# 02_-_Buttons.net
KiCad netlist of a schematic drawn in Altium Designer
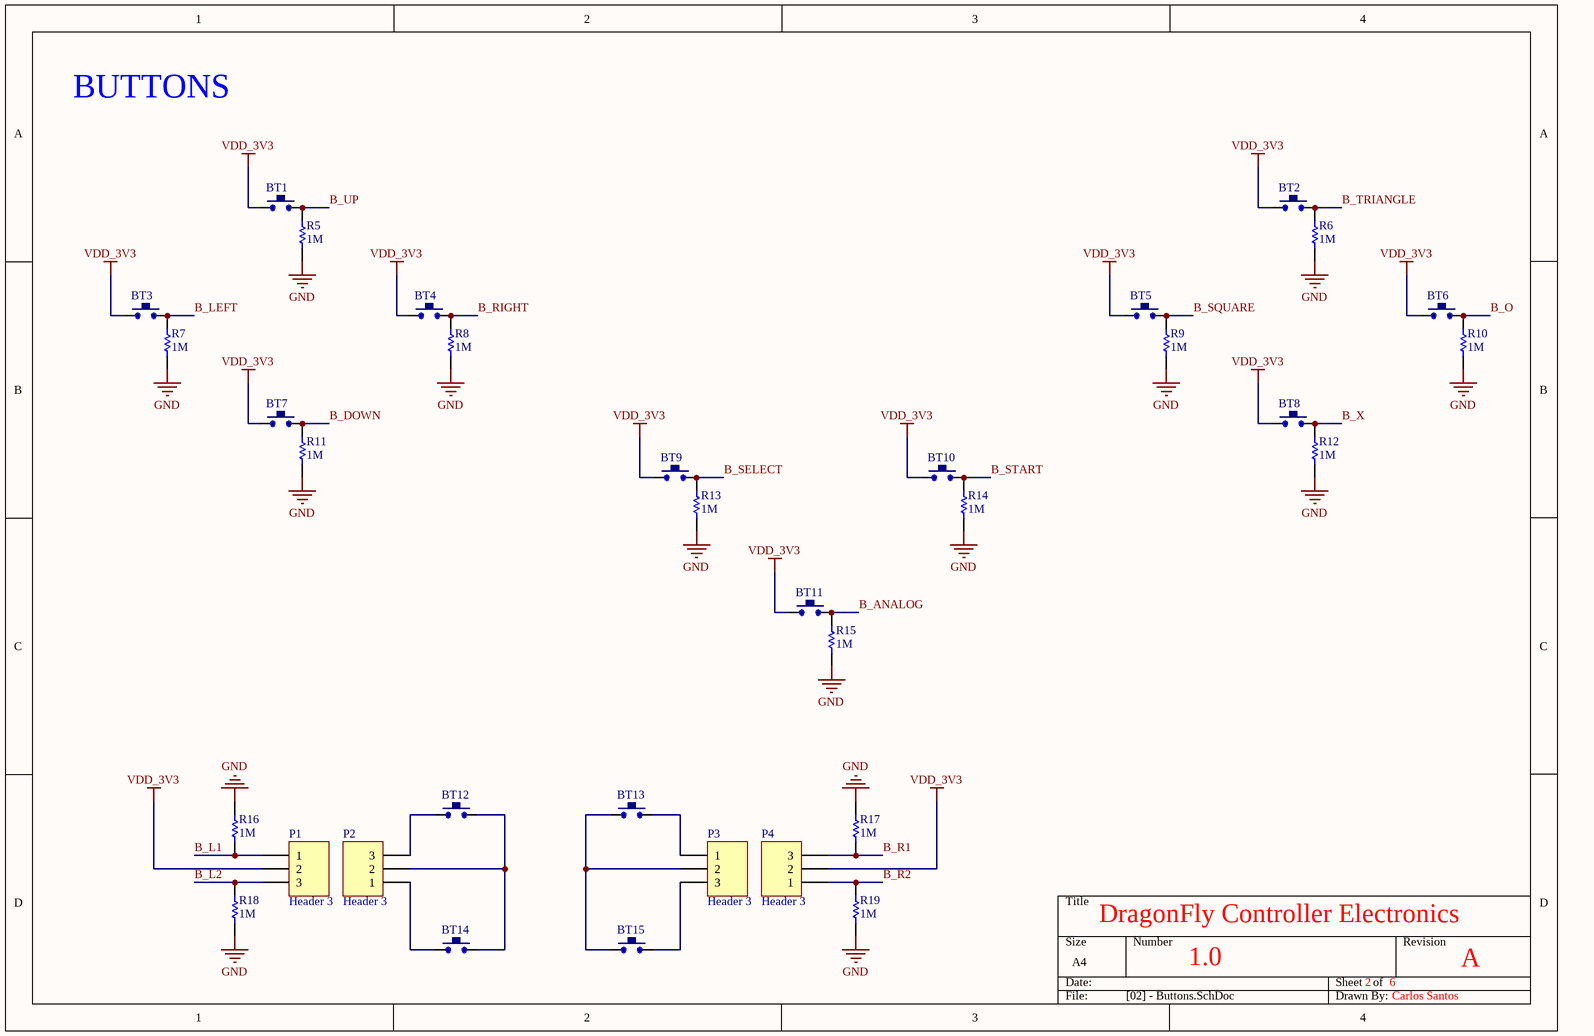
[diagram p0: [02] - Buttons.SchDoc]

(export (version "E")
  (design (tool "Eeschema 10.0.6"))
  (components
    (comp (ref "BT1")
      (value "~")
      (footprint "PCB_button_6mm_round")
      (libsource (lib "Mine") (part "PCB button"))
    )
    (comp (ref "BT2")
      (value "~")
      (footprint "PCB_button_6mm_round")
      (libsource (lib "Mine") (part "PCB button"))
    )
    (comp (ref "BT3")
      (value "~")
      (footprint "PCB_button_6mm_round")
      (libsource (lib "Mine") (part "PCB button"))
    )
    (comp (ref "BT4")
      (value "~")
      (footprint "PCB_button_6mm_round")
      (libsource (lib "Mine") (part "PCB button"))
    )
    (comp (ref "BT5")
      (value "~")
      (footprint "PCB_button_6mm_round")
      (libsource (lib "Mine") (part "PCB button"))
    )
    (comp (ref "BT6")
      (value "~")
      (footprint "PCB_button_6mm_round")
      (libsource (lib "Mine") (part "PCB button"))
    )
    (comp (ref "BT7")
      (value "~")
      (footprint "PCB_button_6mm_round")
      (libsource (lib "Mine") (part "PCB button"))
    )
    (comp (ref "BT8")
      (value "~")
      (footprint "PCB_button_6mm_round")
      (libsource (lib "Mine") (part "PCB button"))
    )
    (comp (ref "BT9")
      (value "~")
      (footprint "PCB_button_10x6mm_rect")
      (libsource (lib "Mine") (part "PCB button"))
    )
    (comp (ref "BT10")
      (value "~")
      (footprint "PCB_button_10x6mm_rect")
      (libsource (lib "Mine") (part "PCB button"))
    )
    (comp (ref "BT11")
      (value "~")
      (footprint "PCB_button_10x6mm_rect")
      (libsource (lib "Mine") (part "PCB button"))
    )
    (comp (ref "BT12")
      (value "~")
      (footprint "PCB_button_10x10mm_rect")
      (libsource (lib "Mine") (part "PCB button"))
    )
    (comp (ref "BT13")
      (value "~")
      (footprint "PCB_button_10x10mm_rect")
      (libsource (lib "Mine") (part "PCB button"))
    )
    (comp (ref "BT14")
      (value "~")
      (footprint "PCB_button_12x10mm_rect")
      (libsource (lib "Mine") (part "PCB button"))
    )
    (comp (ref "BT15")
      (value "~")
      (footprint "PCB_button_12x10mm_rect")
      (libsource (lib "Mine") (part "PCB button"))
    )
    (comp (ref "P1")
      (value "Header 3")
      (footprint "HDR1X3")
      (description "Header, 3-Pin")
      (fields (field (name "PUBLISHER") "Altium Limited"))
      (libsource (lib "") (part "Header 3_1"))
    )
    (comp (ref "P2")
      (value "Header 3")
      (footprint "HDR1X3")
      (description "Header, 3-Pin")
      (fields (field (name "PUBLISHER") "Altium Limited"))
      (libsource (lib "Miscellaneous Connectors") (part "Header 3"))
    )
    (comp (ref "P3")
      (value "Header 3")
      (footprint "HDR1X3")
      (description "Header, 3-Pin")
      (fields (field (name "PUBLISHER") "Altium Limited"))
      (libsource (lib "") (part "Header 3_1"))
    )
    (comp (ref "P4")
      (value "Header 3")
      (footprint "HDR1X3")
      (description "Header, 3-Pin")
      (fields (field (name "PUBLISHER") "Altium Limited"))
      (libsource (lib "Miscellaneous Connectors") (part "Header 3"))
    )
    (comp (ref "R5")
      (value "1M")
      (footprint "0402 - Resistor")
      (fields (field (name "Comment") "Resistor"))
      (libsource (lib "Mine") (part "Resistor"))
    )
    (comp (ref "R6")
      (value "1M")
      (footprint "0402 - Resistor")
      (fields (field (name "Comment") "Resistor"))
      (libsource (lib "Mine") (part "Resistor"))
    )
    (comp (ref "R7")
      (value "1M")
      (footprint "0402 - Resistor")
      (fields (field (name "Comment") "Resistor"))
      (libsource (lib "Mine") (part "Resistor"))
    )
    (comp (ref "R8")
      (value "1M")
      (footprint "0402 - Resistor")
      (fields (field (name "Comment") "Resistor"))
      (libsource (lib "Mine") (part "Resistor"))
    )
    (comp (ref "R9")
      (value "1M")
      (footprint "0402 - Resistor")
      (fields (field (name "Comment") "Resistor"))
      (libsource (lib "Mine") (part "Resistor"))
    )
    (comp (ref "R10")
      (value "1M")
      (footprint "0402 - Resistor")
      (fields (field (name "Comment") "Resistor"))
      (libsource (lib "Mine") (part "Resistor"))
    )
    (comp (ref "R11")
      (value "1M")
      (footprint "0402 - Resistor")
      (fields (field (name "Comment") "Resistor"))
      (libsource (lib "Mine") (part "Resistor"))
    )
    (comp (ref "R12")
      (value "1M")
      (footprint "0402 - Resistor")
      (fields (field (name "Comment") "Resistor"))
      (libsource (lib "Mine") (part "Resistor"))
    )
    (comp (ref "R13")
      (value "1M")
      (footprint "0402 - Resistor")
      (fields (field (name "Comment") "Resistor"))
      (libsource (lib "Mine") (part "Resistor"))
    )
    (comp (ref "R14")
      (value "1M")
      (footprint "0402 - Resistor")
      (fields (field (name "Comment") "Resistor"))
      (libsource (lib "Mine") (part "Resistor"))
    )
    (comp (ref "R15")
      (value "1M")
      (footprint "0402 - Resistor")
      (fields (field (name "Comment") "Resistor"))
      (libsource (lib "Mine") (part "Resistor"))
    )
    (comp (ref "R16")
      (value "1M")
      (footprint "0402 - Resistor")
      (fields (field (name "Comment") "Resistor"))
      (libsource (lib "Mine") (part "Resistor"))
    )
    (comp (ref "R17")
      (value "1M")
      (footprint "0402 - Resistor")
      (fields (field (name "Comment") "Resistor"))
      (libsource (lib "Mine") (part "Resistor"))
    )
    (comp (ref "R18")
      (value "1M")
      (footprint "0402 - Resistor")
      (fields (field (name "Comment") "Resistor"))
      (libsource (lib "Mine") (part "Resistor"))
    )
    (comp (ref "R19")
      (value "1M")
      (footprint "0402 - Resistor")
      (fields (field (name "Comment") "Resistor"))
      (libsource (lib "Mine") (part "Resistor"))
    )
  )
  (nets
    (net (code "1") (name "/B_ANALOG") (class "Default")
      (node (ref "BT11") (pin "2") (pinfunction "2_2") (pintype "passive"))
      (node (ref "R15") (pin "2") (pinfunction "2_2") (pintype "passive"))
    )
    (net (code "2") (name "/B_DOWN") (class "Default")
      (node (ref "BT7") (pin "2") (pinfunction "2_2") (pintype "passive"))
      (node (ref "R11") (pin "2") (pinfunction "2_2") (pintype "passive"))
    )
    (net (code "3") (name "/B_L1") (class "Default")
      (node (ref "P1") (pin "1") (pinfunction "1_1") (pintype "passive"))
      (node (ref "R16") (pin "1") (pinfunction "1_1") (pintype "passive"))
    )
    (net (code "4") (name "/B_L2") (class "Default")
      (node (ref "P1") (pin "3") (pinfunction "3_3") (pintype "passive"))
      (node (ref "R18") (pin "2") (pinfunction "2_2") (pintype "passive"))
    )
    (net (code "5") (name "/B_LEFT") (class "Default")
      (node (ref "BT3") (pin "2") (pinfunction "2_2") (pintype "passive"))
      (node (ref "R7") (pin "2") (pinfunction "2_2") (pintype "passive"))
    )
    (net (code "6") (name "/B_O") (class "Default")
      (node (ref "BT6") (pin "2") (pinfunction "2_2") (pintype "passive"))
      (node (ref "R10") (pin "2") (pinfunction "2_2") (pintype "passive"))
    )
    (net (code "7") (name "/B_R1") (class "Default")
      (node (ref "P4") (pin "3") (pinfunction "3_3") (pintype "passive"))
      (node (ref "R17") (pin "1") (pinfunction "1_1") (pintype "passive"))
    )
    (net (code "8") (name "/B_R2") (class "Default")
      (node (ref "P4") (pin "1") (pinfunction "1_1") (pintype "passive"))
      (node (ref "R19") (pin "2") (pinfunction "2_2") (pintype "passive"))
    )
    (net (code "9") (name "/B_RIGHT") (class "Default")
      (node (ref "BT4") (pin "2") (pinfunction "2_2") (pintype "passive"))
      (node (ref "R8") (pin "2") (pinfunction "2_2") (pintype "passive"))
    )
    (net (code "10") (name "/B_SELECT") (class "Default")
      (node (ref "BT9") (pin "2") (pinfunction "2_2") (pintype "passive"))
      (node (ref "R13") (pin "2") (pinfunction "2_2") (pintype "passive"))
    )
    (net (code "11") (name "/B_SQUARE") (class "Default")
      (node (ref "BT5") (pin "2") (pinfunction "2_2") (pintype "passive"))
      (node (ref "R9") (pin "2") (pinfunction "2_2") (pintype "passive"))
    )
    (net (code "12") (name "/B_START") (class "Default")
      (node (ref "BT10") (pin "2") (pinfunction "2_2") (pintype "passive"))
      (node (ref "R14") (pin "2") (pinfunction "2_2") (pintype "passive"))
    )
    (net (code "13") (name "/B_TRIANGLE") (class "Default")
      (node (ref "BT2") (pin "2") (pinfunction "2_2") (pintype "passive"))
      (node (ref "R6") (pin "2") (pinfunction "2_2") (pintype "passive"))
    )
    (net (code "14") (name "/B_UP") (class "Default")
      (node (ref "BT1") (pin "2") (pinfunction "2_2") (pintype "passive"))
      (node (ref "R5") (pin "2") (pinfunction "2_2") (pintype "passive"))
    )
    (net (code "15") (name "/B_X") (class "Default")
      (node (ref "BT8") (pin "2") (pinfunction "2_2") (pintype "passive"))
      (node (ref "R12") (pin "2") (pinfunction "2_2") (pintype "passive"))
    )
    (net (code "16") (name "GND") (class "Default")
      (node (ref "R10") (pin "1") (pinfunction "1_1") (pintype "passive"))
      (node (ref "R11") (pin "1") (pinfunction "1_1") (pintype "passive"))
      (node (ref "R12") (pin "1") (pinfunction "1_1") (pintype "passive"))
      (node (ref "R13") (pin "1") (pinfunction "1_1") (pintype "passive"))
      (node (ref "R14") (pin "1") (pinfunction "1_1") (pintype "passive"))
      (node (ref "R15") (pin "1") (pinfunction "1_1") (pintype "passive"))
      (node (ref "R16") (pin "2") (pinfunction "2_2") (pintype "passive"))
      (node (ref "R17") (pin "2") (pinfunction "2_2") (pintype "passive"))
      (node (ref "R18") (pin "1") (pinfunction "1_1") (pintype "passive"))
      (node (ref "R19") (pin "1") (pinfunction "1_1") (pintype "passive"))
      (node (ref "R5") (pin "1") (pinfunction "1_1") (pintype "passive"))
      (node (ref "R6") (pin "1") (pinfunction "1_1") (pintype "passive"))
      (node (ref "R7") (pin "1") (pinfunction "1_1") (pintype "passive"))
      (node (ref "R8") (pin "1") (pinfunction "1_1") (pintype "passive"))
      (node (ref "R9") (pin "1") (pinfunction "1_1") (pintype "passive"))
    )
    (net (code "17") (name "Net-(BT12-Pad1)") (class "Default")
      (node (ref "BT12") (pin "1") (pinfunction "1_1") (pintype "passive"))
      (node (ref "P2") (pin "3") (pinfunction "3_3") (pintype "passive"))
    )
    (net (code "18") (name "Net-(BT12-Pad2)") (class "Default")
      (node (ref "BT12") (pin "2") (pinfunction "2_2") (pintype "passive"))
      (node (ref "BT14") (pin "2") (pinfunction "2_2") (pintype "passive"))
      (node (ref "P2") (pin "2") (pinfunction "2_2") (pintype "passive"))
    )
    (net (code "19") (name "Net-(BT13-Pad1)") (class "Default")
      (node (ref "BT13") (pin "1") (pinfunction "1_1") (pintype "passive"))
      (node (ref "BT15") (pin "1") (pinfunction "1_1") (pintype "passive"))
      (node (ref "P3") (pin "2") (pinfunction "2_2") (pintype "passive"))
    )
    (net (code "20") (name "Net-(BT13-Pad2)") (class "Default")
      (node (ref "BT13") (pin "2") (pinfunction "2_2") (pintype "passive"))
      (node (ref "P3") (pin "1") (pinfunction "1_1") (pintype "passive"))
    )
    (net (code "21") (name "Net-(BT14-Pad1)") (class "Default")
      (node (ref "BT14") (pin "1") (pinfunction "1_1") (pintype "passive"))
      (node (ref "P2") (pin "1") (pinfunction "1_1") (pintype "passive"))
    )
    (net (code "22") (name "Net-(BT15-Pad2)") (class "Default")
      (node (ref "BT15") (pin "2") (pinfunction "2_2") (pintype "passive"))
      (node (ref "P3") (pin "3") (pinfunction "3_3") (pintype "passive"))
    )
    (net (code "23") (name "VDD_3V3") (class "Default")
      (node (ref "BT1") (pin "1") (pinfunction "1_1") (pintype "passive"))
      (node (ref "BT10") (pin "1") (pinfunction "1_1") (pintype "passive"))
      (node (ref "BT11") (pin "1") (pinfunction "1_1") (pintype "passive"))
      (node (ref "BT2") (pin "1") (pinfunction "1_1") (pintype "passive"))
      (node (ref "BT3") (pin "1") (pinfunction "1_1") (pintype "passive"))
      (node (ref "BT4") (pin "1") (pinfunction "1_1") (pintype "passive"))
      (node (ref "BT5") (pin "1") (pinfunction "1_1") (pintype "passive"))
      (node (ref "BT6") (pin "1") (pinfunction "1_1") (pintype "passive"))
      (node (ref "BT7") (pin "1") (pinfunction "1_1") (pintype "passive"))
      (node (ref "BT8") (pin "1") (pinfunction "1_1") (pintype "passive"))
      (node (ref "BT9") (pin "1") (pinfunction "1_1") (pintype "passive"))
      (node (ref "P1") (pin "2") (pinfunction "2_2") (pintype "passive"))
      (node (ref "P4") (pin "2") (pinfunction "2_2") (pintype "passive"))
    )
  )
)
